# k26_baseboard_sensors.net
KiCad netlist of a schematic drawn in Altium Designer
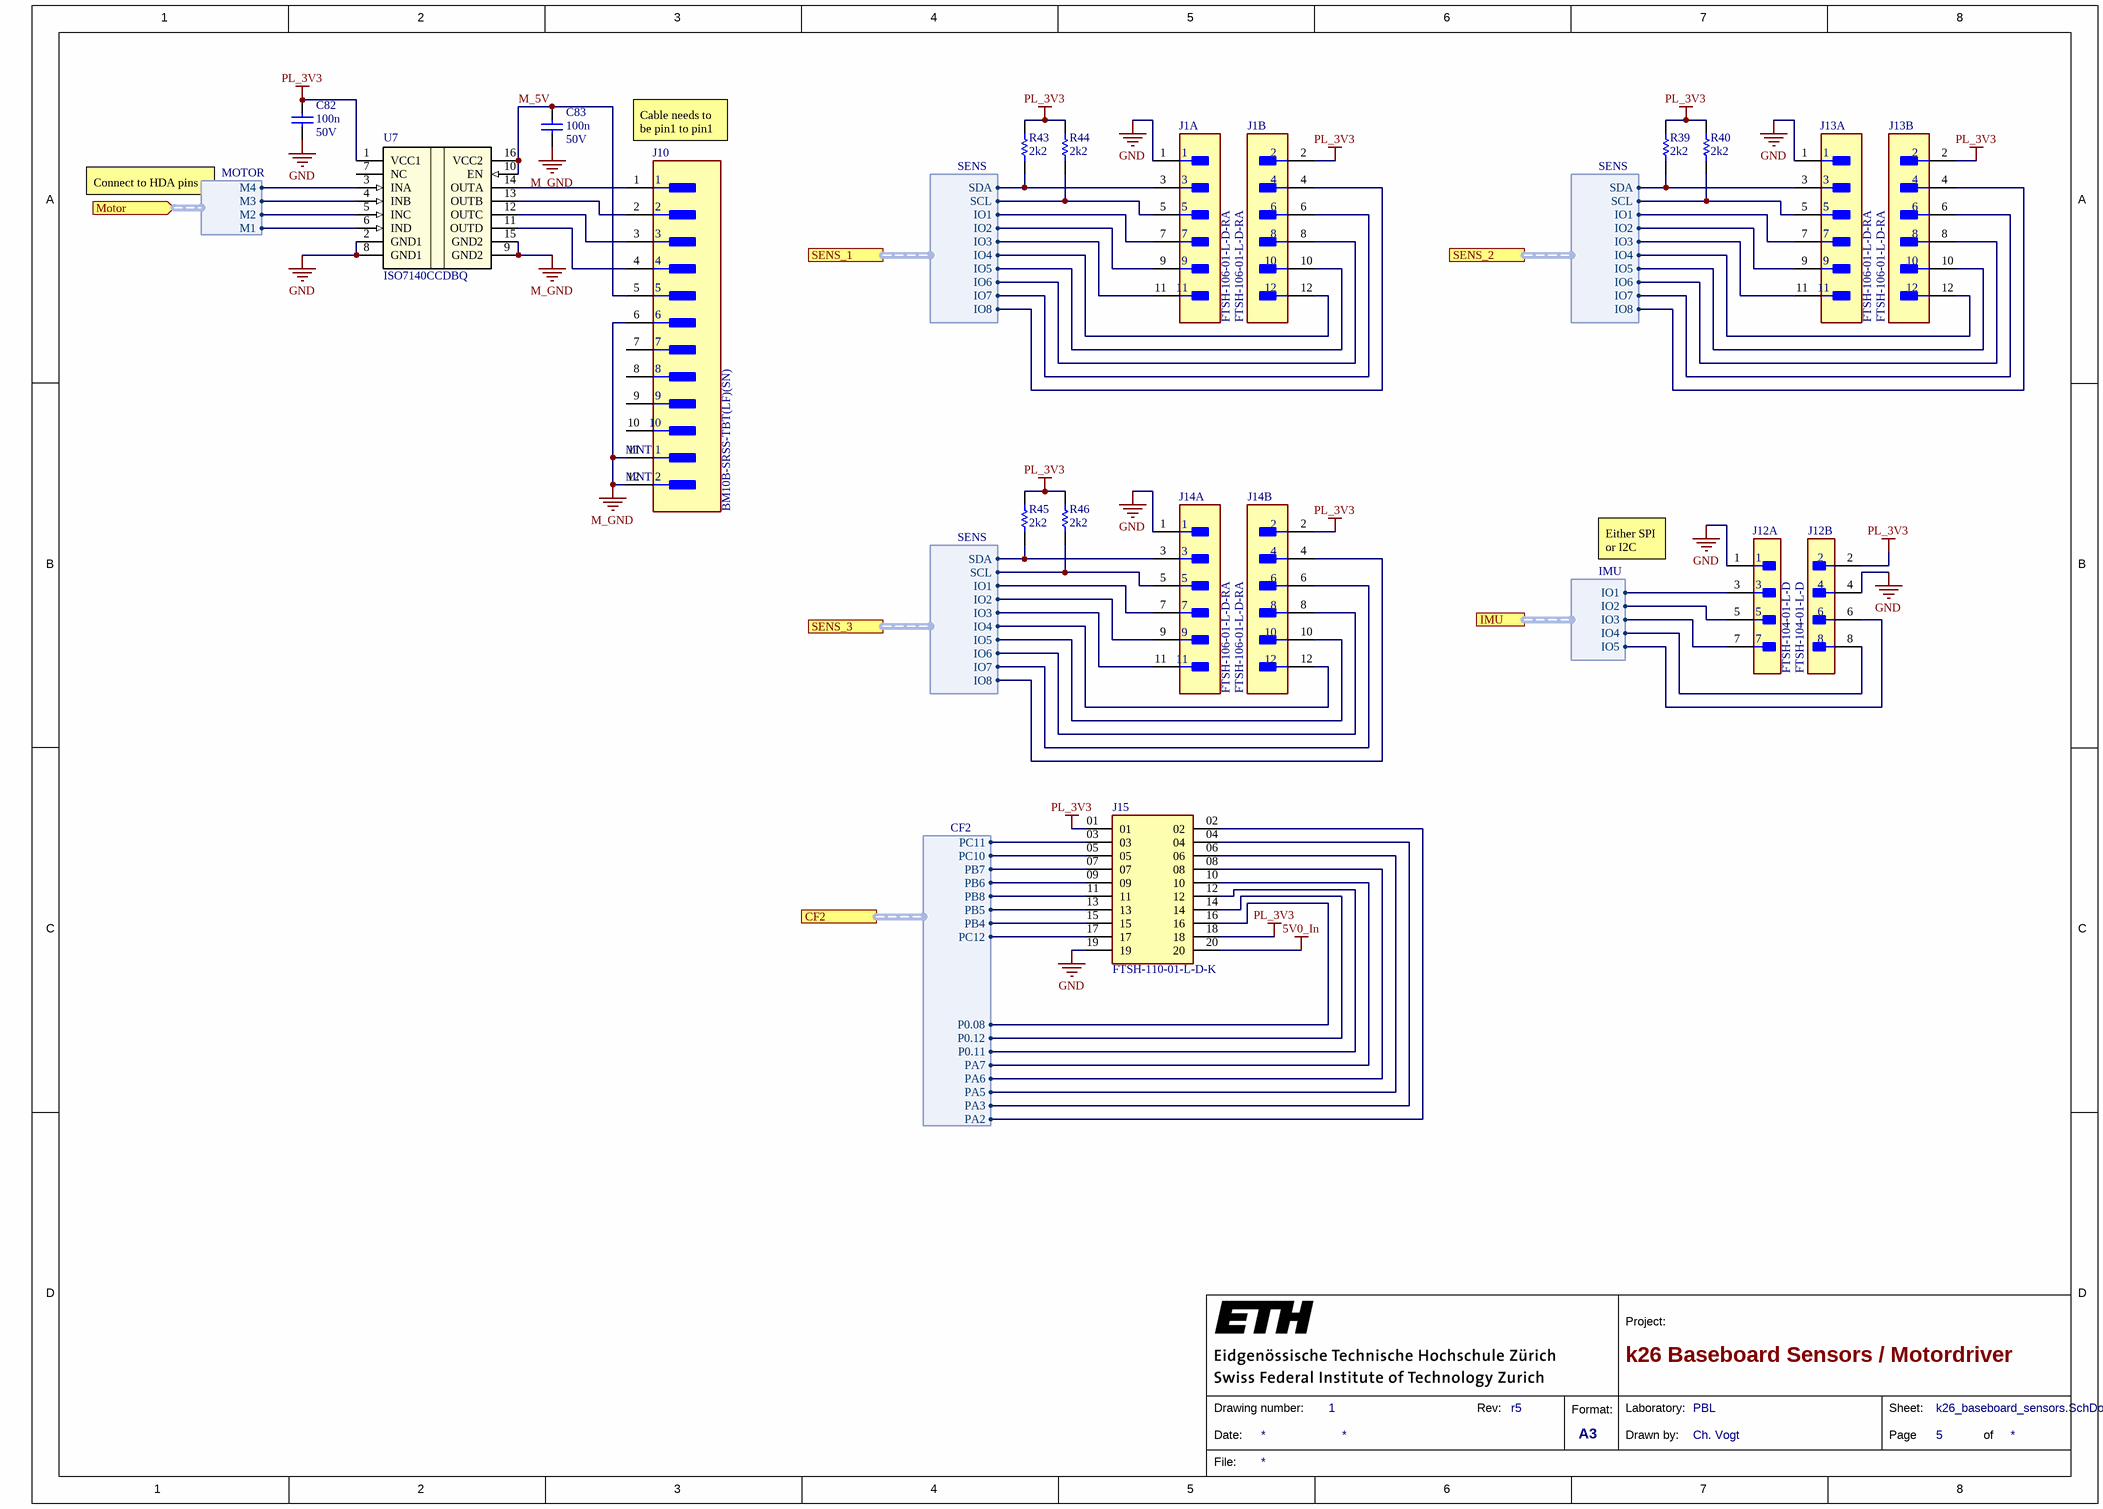
[diagram p0: k26_baseboard_sensors.SchDoc]

(export (version "E")
  (design (tool "Eeschema 10.0.6"))
  (components
    (comp (ref "C82")
      (value "100n")
      (footprint "k26_FPGA_drone_baseboard:CAPC0402")
      (fields
        (field (name "MANUFACTURER") "Yageo")
        (field (name "MANUFACTURER PART NUMBER") "CC0402KRX5R9BB104")
        (field (name "RATED DC VOLTAGE (URDC)") "50V")
      )
      (libsource (lib "k26_FPGA_drone_baseboard") (part "cap0402"))
    )
    (comp (ref "C83")
      (value "100n")
      (footprint "k26_FPGA_drone_baseboard:CAPC0402")
      (fields
        (field (name "MANUFACTURER") "Yageo")
        (field (name "MANUFACTURER PART NUMBER") "CC0402KRX5R9BB104")
        (field (name "RATED DC VOLTAGE (URDC)") "50V")
      )
      (libsource (lib "k26_FPGA_drone_baseboard") (part "cap0402"))
    )
    (comp (ref "J1")
      (value "FTSH-106-01-L-D-RA")
      (footprint "FP-FTSH-106-01-L-D-RA-MFG")
      (description "FTSH-106-01-L-D-RA Conn, R/A Header, 12Pos, 2Row, 1.27Mm Rohs Compliant: Yes")
      (libsource (lib "") (part "803cea653fbe7ecf087c1bc3cef566d_1"))
    )
    (comp (ref "J10")
      (value "BM10B-SRSS-TBT(LF)(SN)")
      (footprint "FP-BM10B-SRSS-TBT_LF_SN-MFG")
      (description "CONN HEADER SMD 10POS 1MM")
      (libsource (lib "k26_FPGA_drone_baseboard") (part "4358d761beece324025ff747d5ae47c"))
    )
    (comp (ref "J12")
      (value "FTSH-104-01-L-D")
      (footprint "FP-FTSH-104-01-L-D-MFG")
      (description "CONN HEADER VERT 8POS 1.27MM")
      (libsource (lib "Altium Content Vault") (part "811e954b9c034aa737de4d9295cbe7e"))
    )
    (comp (ref "J13")
      (value "FTSH-106-01-L-D-RA")
      (footprint "FP-FTSH-106-01-L-D-RA-MFG")
      (description "FTSH-106-01-L-D-RA Conn, R/A Header, 12Pos, 2Row, 1.27Mm Rohs Compliant: Yes")
      (libsource (lib "Altium Content Vault") (part "803cea653fbe7ecf087c1bc3cef566d"))
    )
    (comp (ref "J14")
      (value "FTSH-106-01-L-D-RA")
      (footprint "FP-FTSH-106-01-L-D-RA-MFG")
      (description "FTSH-106-01-L-D-RA Conn, R/A Header, 12Pos, 2Row, 1.27Mm Rohs Compliant: Yes")
      (libsource (lib "") (part "803cea653fbe7ecf087c1bc3cef566d_1"))
    )
    (comp (ref "J15")
      (value "FTSH-110-01-L-D-K")
      (footprint "SAMTEC_FTSH-110-01-L-D-K")
      (libsource (lib "k26_FPGA_drone_baseboard") (part "FTSH-110-01-L-D-K"))
    )
    (comp (ref "R39")
      (value "2k2")
      (footprint "k26_FPGA_drone_baseboard:RES0402")
      (fields
        (field (name "MANUFACTURER") "Vishay")
        (field (name "MANUFACTURER PART NUMBER") "CRCW04022K20FKED")
        (field (name "TOLERANCE") "1%")
      )
      (libsource (lib "k26_FPGA_drone_baseboard") (part "res0402"))
    )
    (comp (ref "R40")
      (value "2k2")
      (footprint "k26_FPGA_drone_baseboard:RES0402")
      (fields
        (field (name "MANUFACTURER") "Vishay")
        (field (name "MANUFACTURER PART NUMBER") "CRCW04022K20FKED")
        (field (name "TOLERANCE") "1%")
      )
      (libsource (lib "k26_FPGA_drone_baseboard") (part "res0402"))
    )
    (comp (ref "R43")
      (value "2k2")
      (footprint "k26_FPGA_drone_baseboard:RES0402")
      (fields
        (field (name "MANUFACTURER") "Vishay")
        (field (name "MANUFACTURER PART NUMBER") "CRCW04022K20FKED")
        (field (name "TOLERANCE") "1%")
      )
      (libsource (lib "k26_FPGA_drone_baseboard") (part "res0402"))
    )
    (comp (ref "R44")
      (value "2k2")
      (footprint "k26_FPGA_drone_baseboard:RES0402")
      (fields
        (field (name "MANUFACTURER") "Vishay")
        (field (name "MANUFACTURER PART NUMBER") "CRCW04022K20FKED")
        (field (name "TOLERANCE") "1%")
      )
      (libsource (lib "k26_FPGA_drone_baseboard") (part "res0402"))
    )
    (comp (ref "R45")
      (value "2k2")
      (footprint "k26_FPGA_drone_baseboard:RES0402")
      (fields
        (field (name "MANUFACTURER") "Vishay")
        (field (name "MANUFACTURER PART NUMBER") "CRCW04022K20FKED")
        (field (name "TOLERANCE") "1%")
      )
      (libsource (lib "k26_FPGA_drone_baseboard") (part "res0402"))
    )
    (comp (ref "R46")
      (value "2k2")
      (footprint "k26_FPGA_drone_baseboard:RES0402")
      (fields
        (field (name "MANUFACTURER") "Vishay")
        (field (name "MANUFACTURER PART NUMBER") "CRCW04022K20FKED")
        (field (name "TOLERANCE") "1%")
      )
      (libsource (lib "k26_FPGA_drone_baseboard") (part "res0402"))
    )
    (comp (ref "U7")
      (value "ISO7140CCDBQ")
      (footprint "DBQ0016A")
      (description "No Description Available")
      (fields (field (name "MANUFACTURER") "Texas Instruments"))
      (libsource (lib "k26_FPGA_drone_baseboard") (part "ISO7140CCDBQR"))
    )
  )
  (nets
    (net (code "5") (name "/M1") (class "Default")
      (node (ref "U7") (pin "6") (pinfunction "IND_6") (pintype "input"))
    )
    (net (code "6") (name "/M2") (class "Default")
      (node (ref "U7") (pin "5") (pinfunction "INC_5") (pintype "input"))
    )
    (net (code "7") (name "/M3") (class "Default")
      (node (ref "U7") (pin "4") (pinfunction "INB_4") (pintype "input"))
    )
    (net (code "8") (name "/M4") (class "Default")
      (node (ref "U7") (pin "3") (pinfunction "INA_3") (pintype "input"))
    )
    (net (code "9") (name "/M_5V") (class "Default")
      (node (ref "C83") (pin "2") (pinfunction "2_2") (pintype "passive"))
      (node (ref "J10") (pin "5") (pinfunction "5_5") (pintype "passive"))
      (node (ref "U7") (pin "10") (pinfunction "EN_10") (pintype "input"))
      (node (ref "U7") (pin "16") (pinfunction "VCC2_16") (pintype "power_in"))
    )
    (net (code "10") (name "/P0.08") (class "Default")
      (node (ref "J15") (pin "16") (pinfunction "16_16") (pintype "passive"))
    )
    (net (code "11") (name "/P0.11") (class "Default")
      (node (ref "J15") (pin "12") (pinfunction "12_12") (pintype "passive"))
    )
    (net (code "12") (name "/P0.12") (class "Default")
      (node (ref "J15") (pin "14") (pinfunction "14_14") (pintype "passive"))
    )
    (net (code "13") (name "/PA2") (class "Default")
      (node (ref "J15") (pin "02") (pinfunction "02_02") (pintype "passive"))
    )
    (net (code "14") (name "/PA3") (class "Default")
      (node (ref "J15") (pin "04") (pinfunction "04_04") (pintype "passive"))
    )
    (net (code "15") (name "/PA5") (class "Default")
      (node (ref "J15") (pin "06") (pinfunction "06_06") (pintype "passive"))
    )
    (net (code "16") (name "/PA6") (class "Default")
      (node (ref "J15") (pin "08") (pinfunction "08_08") (pintype "passive"))
    )
    (net (code "17") (name "/PA7") (class "Default")
      (node (ref "J15") (pin "10") (pinfunction "10_10") (pintype "passive"))
    )
    (net (code "18") (name "/PB4") (class "Default")
      (node (ref "J15") (pin "15") (pinfunction "15_15") (pintype "passive"))
    )
    (net (code "19") (name "/PB5") (class "Default")
      (node (ref "J15") (pin "13") (pinfunction "13_13") (pintype "passive"))
    )
    (net (code "20") (name "/PB6") (class "Default")
      (node (ref "J15") (pin "09") (pinfunction "09_09") (pintype "passive"))
    )
    (net (code "21") (name "/PB7") (class "Default")
      (node (ref "J15") (pin "07") (pinfunction "07_07") (pintype "passive"))
    )
    (net (code "22") (name "/PB8") (class "Default")
      (node (ref "J15") (pin "11") (pinfunction "11_11") (pintype "passive"))
    )
    (net (code "23") (name "/PC10") (class "Default")
      (node (ref "J15") (pin "05") (pinfunction "05_05") (pintype "passive"))
    )
    (net (code "24") (name "/PC11") (class "Default")
      (node (ref "J15") (pin "03") (pinfunction "03_03") (pintype "passive"))
    )
    (net (code "25") (name "/PC12") (class "Default")
      (node (ref "J15") (pin "17") (pinfunction "17_17") (pintype "passive"))
    )
    (net (code "30") (name "5V0_In") (class "Default")
      (node (ref "J15") (pin "20") (pinfunction "20_20") (pintype "passive"))
    )
    (net (code "31") (name "GND") (class "Default")
      (node (ref "C82") (pin "1") (pinfunction "1_1") (pintype "passive"))
      (node (ref "J1") (pin "1") (pinfunction "1_1") (pintype "passive"))
      (node (ref "J12") (pin "1") (pinfunction "1_1") (pintype "passive"))
      (node (ref "J12") (pin "4") (pinfunction "4_4") (pintype "passive"))
      (node (ref "J13") (pin "1") (pinfunction "1_1") (pintype "passive"))
      (node (ref "J14") (pin "1") (pinfunction "1_1") (pintype "passive"))
      (node (ref "J15") (pin "19") (pinfunction "19_19") (pintype "passive"))
      (node (ref "U7") (pin "2") (pinfunction "GND1_2") (pintype "power_in"))
      (node (ref "U7") (pin "8") (pinfunction "GND1_8") (pintype "power_in"))
    )
    (net (code "32") (name "M_GND") (class "Default")
      (node (ref "C83") (pin "1") (pinfunction "1_1") (pintype "passive"))
      (node (ref "J10") (pin "11") (pinfunction "MNT_1_11") (pintype "passive"))
      (node (ref "J10") (pin "12") (pinfunction "MNT_2_12") (pintype "passive"))
      (node (ref "J10") (pin "6") (pinfunction "6_6") (pintype "passive"))
      (node (ref "U7") (pin "15") (pinfunction "GND2_15") (pintype "power_in"))
      (node (ref "U7") (pin "9") (pinfunction "GND2_9") (pintype "power_in"))
    )
    (net (code "33") (name "Net-(J1-Pad3)") (class "Default")
      (node (ref "J1") (pin "3") (pinfunction "3_3") (pintype "passive"))
      (node (ref "R43") (pin "1") (pinfunction "1_1") (pintype "passive"))
    )
    (net (code "34") (name "Net-(J1-Pad5)") (class "Default")
      (node (ref "J1") (pin "5") (pinfunction "5_5") (pintype "passive"))
      (node (ref "R44") (pin "1") (pinfunction "1_1") (pintype "passive"))
    )
    (net (code "35") (name "Net-(J13-Pad3)") (class "Default")
      (node (ref "J13") (pin "3") (pinfunction "3_3") (pintype "passive"))
      (node (ref "R39") (pin "1") (pinfunction "1_1") (pintype "passive"))
    )
    (net (code "36") (name "Net-(J13-Pad5)") (class "Default")
      (node (ref "J13") (pin "5") (pinfunction "5_5") (pintype "passive"))
      (node (ref "R40") (pin "1") (pinfunction "1_1") (pintype "passive"))
    )
    (net (code "37") (name "Net-(J14-Pad3)") (class "Default")
      (node (ref "J14") (pin "3") (pinfunction "3_3") (pintype "passive"))
      (node (ref "R45") (pin "1") (pinfunction "1_1") (pintype "passive"))
    )
    (net (code "38") (name "Net-(J14-Pad5)") (class "Default")
      (node (ref "J14") (pin "5") (pinfunction "5_5") (pintype "passive"))
      (node (ref "R46") (pin "1") (pinfunction "1_1") (pintype "passive"))
    )
    (net (code "39") (name "Net-(U7-OUTA)") (class "Default")
      (node (ref "J10") (pin "1") (pinfunction "1_1") (pintype "passive"))
      (node (ref "U7") (pin "14") (pinfunction "OUTA_14") (pintype "tri_state"))
    )
    (net (code "40") (name "Net-(U7-OUTB)") (class "Default")
      (node (ref "J10") (pin "2") (pinfunction "2_2") (pintype "passive"))
      (node (ref "U7") (pin "13") (pinfunction "OUTB_13") (pintype "tri_state"))
    )
    (net (code "41") (name "Net-(U7-OUTC)") (class "Default")
      (node (ref "J10") (pin "3") (pinfunction "3_3") (pintype "passive"))
      (node (ref "U7") (pin "12") (pinfunction "OUTC_12") (pintype "tri_state"))
    )
    (net (code "42") (name "Net-(U7-OUTD)") (class "Default")
      (node (ref "J10") (pin "4") (pinfunction "4_4") (pintype "passive"))
      (node (ref "U7") (pin "11") (pinfunction "OUTD_11") (pintype "tri_state"))
    )
    (net (code "43") (name "PL_3V3") (class "Default")
      (node (ref "C82") (pin "2") (pinfunction "2_2") (pintype "passive"))
      (node (ref "J1") (pin "2") (pinfunction "2_2") (pintype "passive"))
      (node (ref "J12") (pin "2") (pinfunction "2_2") (pintype "passive"))
      (node (ref "J13") (pin "2") (pinfunction "2_2") (pintype "passive"))
      (node (ref "J14") (pin "2") (pinfunction "2_2") (pintype "passive"))
      (node (ref "J15") (pin "01") (pinfunction "01_01") (pintype "passive"))
      (node (ref "J15") (pin "18") (pinfunction "18_18") (pintype "passive"))
      (node (ref "R39") (pin "2") (pinfunction "2_2") (pintype "passive"))
      (node (ref "R40") (pin "2") (pinfunction "2_2") (pintype "passive"))
      (node (ref "R43") (pin "2") (pinfunction "2_2") (pintype "passive"))
      (node (ref "R44") (pin "2") (pinfunction "2_2") (pintype "passive"))
      (node (ref "R45") (pin "2") (pinfunction "2_2") (pintype "passive"))
      (node (ref "R46") (pin "2") (pinfunction "2_2") (pintype "passive"))
      (node (ref "U7") (pin "1") (pinfunction "VCC1_1") (pintype "power_in"))
    )
    (net (code "44") (name "unconnected-(J1-Pad4)") (class "Default")
      (node (ref "J1") (pin "4") (pinfunction "4_4") (pintype "passive"))
    )
    (net (code "45") (name "unconnected-(J1-Pad6)") (class "Default")
      (node (ref "J1") (pin "6") (pinfunction "6_6") (pintype "passive"))
    )
    (net (code "46") (name "unconnected-(J1-Pad7)") (class "Default")
      (node (ref "J1") (pin "7") (pinfunction "7_7") (pintype "passive"))
    )
    (net (code "47") (name "unconnected-(J1-Pad8)") (class "Default")
      (node (ref "J1") (pin "8") (pinfunction "8_8") (pintype "passive"))
    )
    (net (code "48") (name "unconnected-(J1-Pad9)") (class "Default")
      (node (ref "J1") (pin "9") (pinfunction "9_9") (pintype "passive"))
    )
    (net (code "49") (name "unconnected-(J1-Pad10)") (class "Default")
      (node (ref "J1") (pin "10") (pinfunction "10_10") (pintype "passive"))
    )
    (net (code "50") (name "unconnected-(J1-Pad11)") (class "Default")
      (node (ref "J1") (pin "11") (pinfunction "11_11") (pintype "passive"))
    )
    (net (code "51") (name "unconnected-(J1-Pad12)") (class "Default")
      (node (ref "J1") (pin "12") (pinfunction "12_12") (pintype "passive"))
    )
    (net (code "52") (name "unconnected-(J10-Pad7)") (class "Default")
      (node (ref "J10") (pin "7") (pinfunction "7_7") (pintype "passive"))
    )
    (net (code "53") (name "unconnected-(J10-Pad8)") (class "Default")
      (node (ref "J10") (pin "8") (pinfunction "8_8") (pintype "passive"))
    )
    (net (code "54") (name "unconnected-(J10-Pad9)") (class "Default")
      (node (ref "J10") (pin "9") (pinfunction "9_9") (pintype "passive"))
    )
    (net (code "55") (name "unconnected-(J10-Pad10)") (class "Default")
      (node (ref "J10") (pin "10") (pinfunction "10_10") (pintype "passive"))
    )
    (net (code "56") (name "unconnected-(J12-Pad3)") (class "Default")
      (node (ref "J12") (pin "3") (pinfunction "3_3") (pintype "passive"))
    )
    (net (code "57") (name "unconnected-(J12-Pad5)") (class "Default")
      (node (ref "J12") (pin "5") (pinfunction "5_5") (pintype "passive"))
    )
    (net (code "58") (name "unconnected-(J12-Pad6)") (class "Default")
      (node (ref "J12") (pin "6") (pinfunction "6_6") (pintype "passive"))
    )
    (net (code "59") (name "unconnected-(J12-Pad7)") (class "Default")
      (node (ref "J12") (pin "7") (pinfunction "7_7") (pintype "passive"))
    )
    (net (code "60") (name "unconnected-(J12-Pad8)") (class "Default")
      (node (ref "J12") (pin "8") (pinfunction "8_8") (pintype "passive"))
    )
    (net (code "61") (name "unconnected-(J13-Pad4)") (class "Default")
      (node (ref "J13") (pin "4") (pinfunction "4_4") (pintype "passive"))
    )
    (net (code "62") (name "unconnected-(J13-Pad6)") (class "Default")
      (node (ref "J13") (pin "6") (pinfunction "6_6") (pintype "passive"))
    )
    (net (code "63") (name "unconnected-(J13-Pad7)") (class "Default")
      (node (ref "J13") (pin "7") (pinfunction "7_7") (pintype "passive"))
    )
    (net (code "64") (name "unconnected-(J13-Pad8)") (class "Default")
      (node (ref "J13") (pin "8") (pinfunction "8_8") (pintype "passive"))
    )
    (net (code "65") (name "unconnected-(J13-Pad9)") (class "Default")
      (node (ref "J13") (pin "9") (pinfunction "9_9") (pintype "passive"))
    )
    (net (code "66") (name "unconnected-(J13-Pad10)") (class "Default")
      (node (ref "J13") (pin "10") (pinfunction "10_10") (pintype "passive"))
    )
    (net (code "67") (name "unconnected-(J13-Pad11)") (class "Default")
      (node (ref "J13") (pin "11") (pinfunction "11_11") (pintype "passive"))
    )
    (net (code "68") (name "unconnected-(J13-Pad12)") (class "Default")
      (node (ref "J13") (pin "12") (pinfunction "12_12") (pintype "passive"))
    )
    (net (code "69") (name "unconnected-(J14-Pad4)") (class "Default")
      (node (ref "J14") (pin "4") (pinfunction "4_4") (pintype "passive"))
    )
    (net (code "70") (name "unconnected-(J14-Pad6)") (class "Default")
      (node (ref "J14") (pin "6") (pinfunction "6_6") (pintype "passive"))
    )
    (net (code "71") (name "unconnected-(J14-Pad7)") (class "Default")
      (node (ref "J14") (pin "7") (pinfunction "7_7") (pintype "passive"))
    )
    (net (code "72") (name "unconnected-(J14-Pad8)") (class "Default")
      (node (ref "J14") (pin "8") (pinfunction "8_8") (pintype "passive"))
    )
    (net (code "73") (name "unconnected-(J14-Pad9)") (class "Default")
      (node (ref "J14") (pin "9") (pinfunction "9_9") (pintype "passive"))
    )
    (net (code "74") (name "unconnected-(J14-Pad10)") (class "Default")
      (node (ref "J14") (pin "10") (pinfunction "10_10") (pintype "passive"))
    )
    (net (code "75") (name "unconnected-(J14-Pad11)") (class "Default")
      (node (ref "J14") (pin "11") (pinfunction "11_11") (pintype "passive"))
    )
    (net (code "76") (name "unconnected-(J14-Pad12)") (class "Default")
      (node (ref "J14") (pin "12") (pinfunction "12_12") (pintype "passive"))
    )
    (net (code "77") (name "unconnected-(U7-NC-Pad7)") (class "Default")
      (node (ref "U7") (pin "7") (pinfunction "NC_7") (pintype "passive"))
    )
  )
)
